# CAN_Adapter_ES_PCB.net
KiCad netlist of a schematic drawn in EAGLE
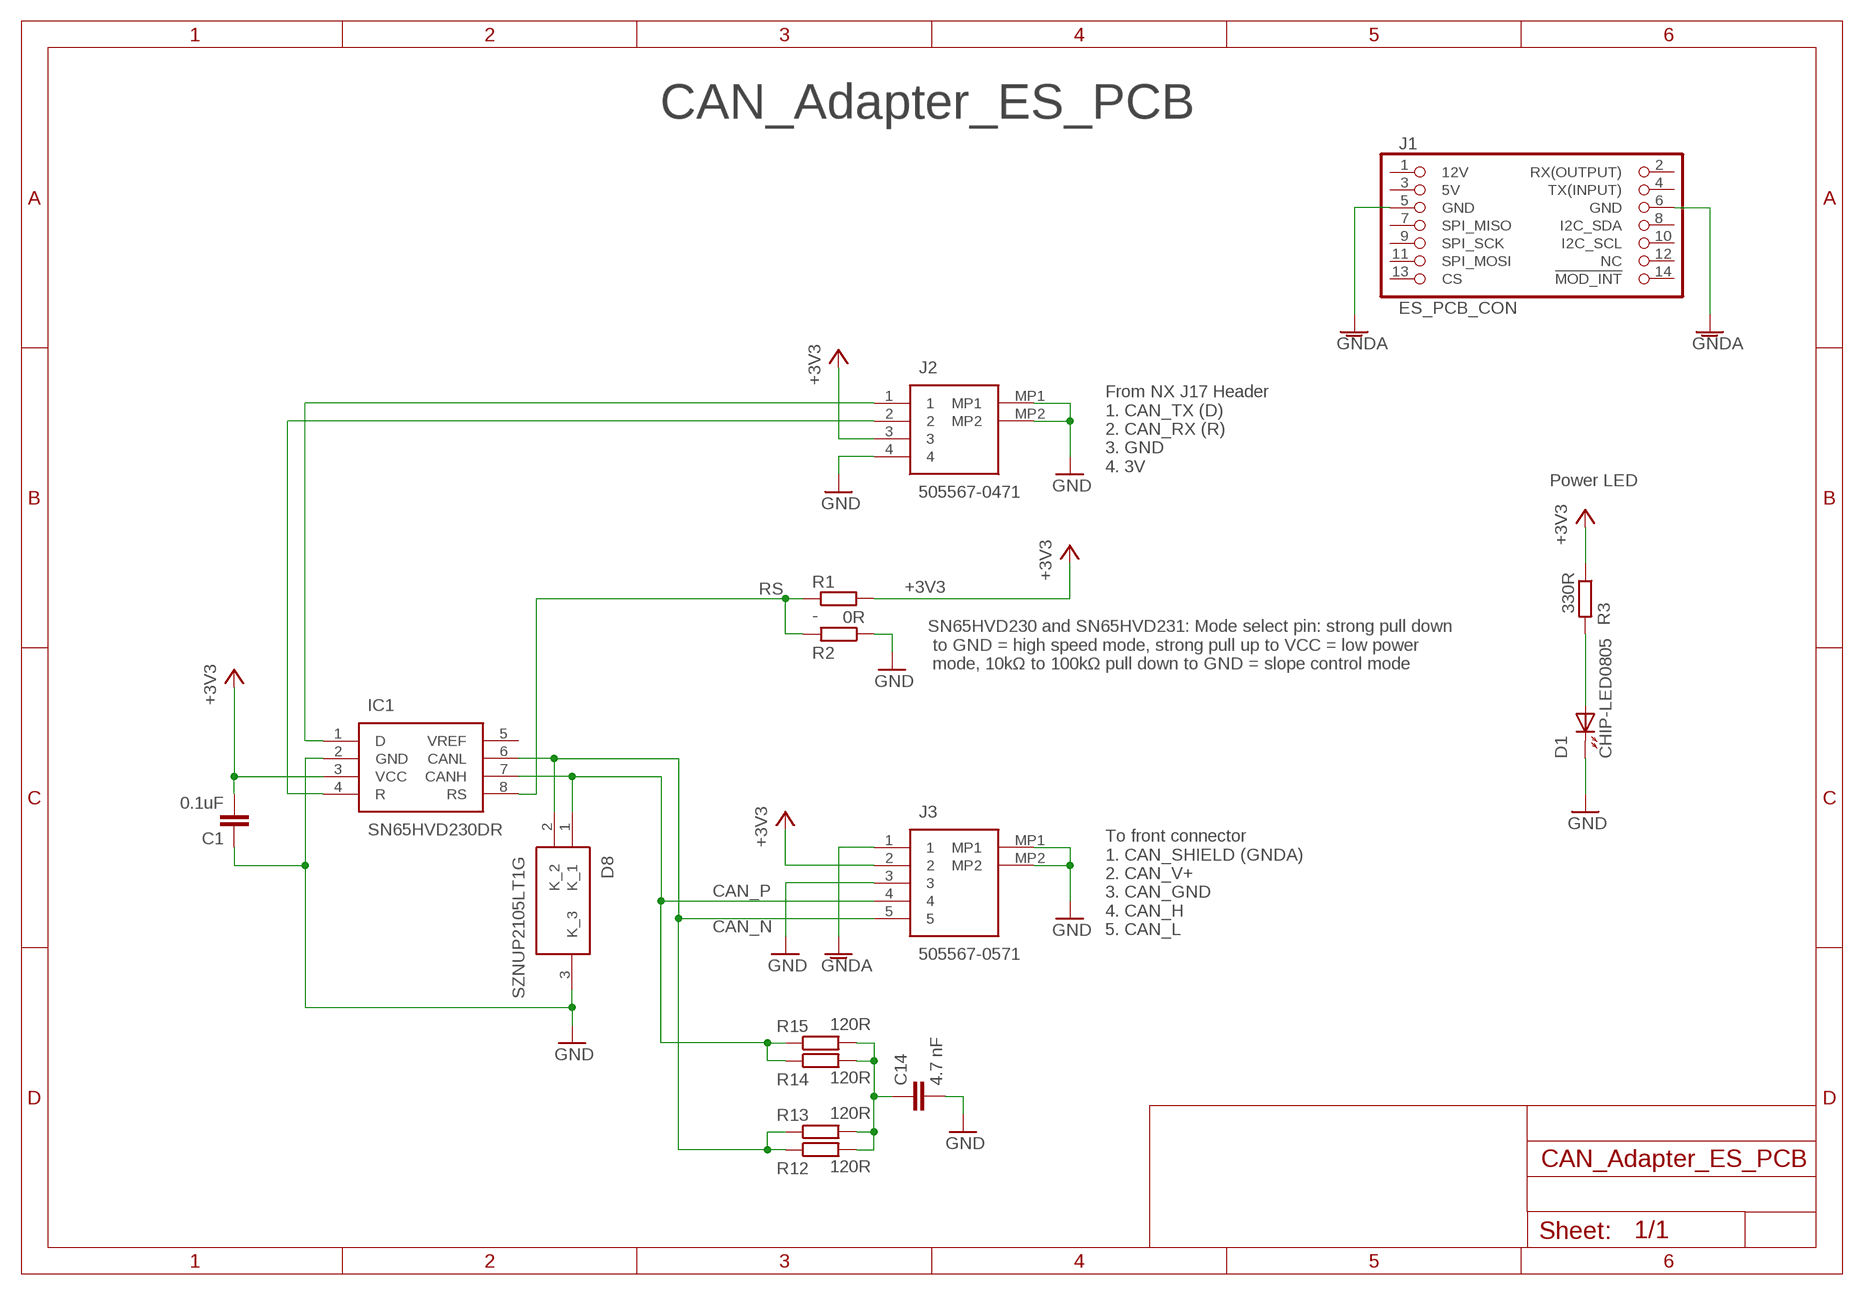
[diagram p0: schematic, sheet 1]

(export (version "E")
  (design (tool "Eeschema 10.0.6"))
  (components
    (comp (ref "C1")
      (value "0.1uF")
      (footprint "eagle-import:C0603")
      (libsource (lib "eagle-import") (part "C0603"))
    )
    (comp (ref "C14")
      (value "4.7 nF")
      (footprint "eagle-import:C0805")
      (libsource (lib "eagle-import") (part "C0805"))
    )
    (comp (ref "D1")
      (value "CHIP-LED0805")
      (footprint "eagle-import:CHIP-LED0805")
      (libsource (lib "eagle-import") (part "CHIP-LED0805"))
    )
    (comp (ref "D8")
      (value "SZNUP2105LT1G")
      (footprint "eagle-import:SOT96P237X111-3N")
      (fields (field (name "MOUSER_PART_NUMBER") "863-SZNUP2105LT1G"))
      (libsource (lib "eagle-import") (part "SZNUP2105LT1G"))
    )
    (comp (ref "IC1")
      (value "SN65HVD230DR")
      (footprint "eagle-import:SOT127P600X175-8N")
      (fields (field (name "MOUSER_PART_NUMBER") "595-SN65HVD230DR"))
      (libsource (lib "eagle-import") (part "SN65HVD230DR"))
    )
    (comp (ref "J1")
      (value "ES_PCB_CON")
      (footprint "eagle-import:ES_PCB_CON")
      (libsource (lib "eagle-import") (part "ES_PCB_CON"))
    )
    (comp (ref "J2")
      (value "505567-0471")
      (footprint "eagle-import:5055680471")
      (libsource (lib "eagle-import") (part "505567-0471"))
    )
    (comp (ref "J3")
      (value "505567-0571")
      (footprint "eagle-import:5055680571")
      (fields
        (field (name "MANUFACTURER_PART_NUMBER") "505568-0571")
        (field (name "RS_PART_NUMBER") "1615926P")
      )
      (libsource (lib "eagle-import") (part "505567-0571"))
    )
    (comp (ref "R1")
      (value "-")
      (footprint "eagle-import:R0603")
      (libsource (lib "eagle-import") (part "R0603"))
    )
    (comp (ref "R2")
      (value "0R")
      (footprint "eagle-import:R0603")
      (libsource (lib "eagle-import") (part "R0603"))
    )
    (comp (ref "R3")
      (value "330R")
      (footprint "eagle-import:R0603")
      (libsource (lib "eagle-import") (part "R0603"))
    )
    (comp (ref "R12")
      (value "120R")
      (footprint "eagle-import:R1210")
      (libsource (lib "eagle-import") (part "R-EU_R1210"))
    )
    (comp (ref "R13")
      (value "120R")
      (footprint "eagle-import:R1210")
      (libsource (lib "eagle-import") (part "R-EU_R1210"))
    )
    (comp (ref "R14")
      (value "120R")
      (footprint "eagle-import:R1210")
      (libsource (lib "eagle-import") (part "R-EU_R1210"))
    )
    (comp (ref "R15")
      (value "120R")
      (footprint "eagle-import:R1210")
      (libsource (lib "eagle-import") (part "R-EU_R1210"))
    )
  )
  (nets
    (net (code "1") (name "+3V3") (class "Default")
      (node (ref "C1") (pin "2") (pinfunction "2_2") (pintype "passive"))
      (node (ref "IC1") (pin "3") (pinfunction "VCC_3") (pintype "bidirectional"))
      (node (ref "J2") (pin "3") (pinfunction "3_3") (pintype "bidirectional"))
      (node (ref "J3") (pin "2") (pinfunction "2_2") (pintype "bidirectional"))
      (node (ref "R1") (pin "2") (pinfunction "2_2") (pintype "passive"))
      (node (ref "R3") (pin "1") (pinfunction "1_1") (pintype "passive"))
    )
    (net (code "2") (name "/CAN_N") (class "Default")
      (node (ref "D8") (pin "2") (pinfunction "K_2_2") (pintype "bidirectional"))
      (node (ref "IC1") (pin "6") (pinfunction "CANL_6") (pintype "bidirectional"))
      (node (ref "J3") (pin "5") (pinfunction "5_5") (pintype "bidirectional"))
      (node (ref "R12") (pin "1") (pinfunction "1_1") (pintype "passive"))
      (node (ref "R13") (pin "1") (pinfunction "1_1") (pintype "passive"))
    )
    (net (code "3") (name "/CAN_P") (class "Default")
      (node (ref "D8") (pin "1") (pinfunction "K_1_1") (pintype "bidirectional"))
      (node (ref "IC1") (pin "7") (pinfunction "CANH_7") (pintype "bidirectional"))
      (node (ref "J3") (pin "4") (pinfunction "4_4") (pintype "bidirectional"))
      (node (ref "R14") (pin "1") (pinfunction "1_1") (pintype "passive"))
      (node (ref "R15") (pin "1") (pinfunction "1_1") (pintype "passive"))
    )
    (net (code "4") (name "/RS") (class "Default")
      (node (ref "IC1") (pin "8") (pinfunction "RS_8") (pintype "bidirectional"))
      (node (ref "R1") (pin "1") (pinfunction "1_1") (pintype "passive"))
      (node (ref "R2") (pin "2") (pinfunction "2_2") (pintype "passive"))
    )
    (net (code "5") (name "GND") (class "Default")
      (node (ref "C1") (pin "1") (pinfunction "1_1") (pintype "passive"))
      (node (ref "C14") (pin "2") (pinfunction "2_2") (pintype "passive"))
      (node (ref "D1") (pin "C") (pinfunction "K_C") (pintype "passive"))
      (node (ref "D8") (pin "3") (pinfunction "K_3_3") (pintype "bidirectional"))
      (node (ref "IC1") (pin "2") (pinfunction "GND_2") (pintype "bidirectional"))
      (node (ref "J2") (pin "4") (pinfunction "4_4") (pintype "bidirectional"))
      (node (ref "J2") (pin "MP1") (pinfunction "MP1_MP1") (pintype "bidirectional"))
      (node (ref "J2") (pin "MP2") (pinfunction "MP2_MP2") (pintype "bidirectional"))
      (node (ref "J3") (pin "3") (pinfunction "3_3") (pintype "bidirectional"))
      (node (ref "J3") (pin "MP1") (pinfunction "MP1_MP1") (pintype "bidirectional"))
      (node (ref "J3") (pin "MP2") (pinfunction "MP2_MP2") (pintype "bidirectional"))
      (node (ref "R2") (pin "1") (pinfunction "1_1") (pintype "passive"))
    )
    (net (code "6") (name "GNDA") (class "Default")
      (node (ref "J1") (pin "5") (pinfunction "GND_5") (pintype "passive"))
      (node (ref "J1") (pin "6") (pinfunction "GND_6") (pintype "passive"))
      (node (ref "J3") (pin "1") (pinfunction "1_1") (pintype "bidirectional"))
    )
    (net (code "7") (name "Net-(C14-Pad1)") (class "Default")
      (node (ref "C14") (pin "1") (pinfunction "1_1") (pintype "passive"))
      (node (ref "R12") (pin "2") (pinfunction "2_2") (pintype "passive"))
      (node (ref "R13") (pin "2") (pinfunction "2_2") (pintype "passive"))
      (node (ref "R14") (pin "2") (pinfunction "2_2") (pintype "passive"))
      (node (ref "R15") (pin "2") (pinfunction "2_2") (pintype "passive"))
    )
    (net (code "8") (name "Net-(D1-PadA)") (class "Default")
      (node (ref "D1") (pin "A") (pinfunction "A_A") (pintype "passive"))
      (node (ref "R3") (pin "2") (pinfunction "2_2") (pintype "passive"))
    )
    (net (code "9") (name "Net-(IC1-D)") (class "Default")
      (node (ref "IC1") (pin "1") (pinfunction "D_1") (pintype "bidirectional"))
      (node (ref "J2") (pin "1") (pinfunction "1_1") (pintype "bidirectional"))
    )
    (net (code "10") (name "Net-(IC1-R)") (class "Default")
      (node (ref "IC1") (pin "4") (pinfunction "R_4") (pintype "bidirectional"))
      (node (ref "J2") (pin "2") (pinfunction "2_2") (pintype "bidirectional"))
    )
    (net (code "11") (name "unconnected-(IC1-VREF-Pad5)") (class "Default")
      (node (ref "IC1") (pin "5") (pinfunction "VREF_5") (pintype "bidirectional"))
    )
    (net (code "12") (name "unconnected-(J1-5V-Pad3)") (class "Default")
      (node (ref "J1") (pin "3") (pinfunction "5V_3") (pintype "passive"))
    )
    (net (code "13") (name "unconnected-(J1-12V-Pad1)") (class "Default")
      (node (ref "J1") (pin "1") (pinfunction "12V_1") (pintype "passive"))
    )
    (net (code "14") (name "unconnected-(J1-CS-Pad13)") (class "Default")
      (node (ref "J1") (pin "13") (pinfunction "CS_13") (pintype "passive"))
    )
    (net (code "15") (name "unconnected-(J1-I2C_SCL-Pad10)") (class "Default")
      (node (ref "J1") (pin "10") (pinfunction "I2C_SCL_10") (pintype "passive"))
    )
    (net (code "16") (name "unconnected-(J1-I2C_SDA-Pad8)") (class "Default")
      (node (ref "J1") (pin "8") (pinfunction "I2C_SDA_8") (pintype "passive"))
    )
    (net (code "17") (name "unconnected-(J1-NC-Pad12)") (class "Default")
      (node (ref "J1") (pin "12") (pinfunction "NC_12") (pintype "passive"))
    )
    (net (code "18") (name "unconnected-(J1-RX(OUTPUT)-Pad2)") (class "Default")
      (node (ref "J1") (pin "2") (pinfunction "RX(OUTPUT)_2") (pintype "passive"))
    )
    (net (code "19") (name "unconnected-(J1-SPI_MISO-Pad7)") (class "Default")
      (node (ref "J1") (pin "7") (pinfunction "SPI_MISO_7") (pintype "passive"))
    )
    (net (code "20") (name "unconnected-(J1-SPI_MOSI-Pad11)") (class "Default")
      (node (ref "J1") (pin "11") (pinfunction "SPI_MOSI_11") (pintype "passive"))
    )
    (net (code "21") (name "unconnected-(J1-SPI_SCK-Pad9)") (class "Default")
      (node (ref "J1") (pin "9") (pinfunction "SPI_SCK_9") (pintype "passive"))
    )
    (net (code "22") (name "unconnected-(J1-TX(INPUT)-Pad4)") (class "Default")
      (node (ref "J1") (pin "4") (pinfunction "TX(INPUT)_4") (pintype "passive"))
    )
    (net (code "23") (name "unconnected-(J1-~{MOD_INT}-Pad14)") (class "Default")
      (node (ref "J1") (pin "14") (pinfunction "~{MOD_INT}_14") (pintype "passive"))
    )
  )
)
